# FCF_v2.net
KiCad netlist of a schematic drawn in EAGLE
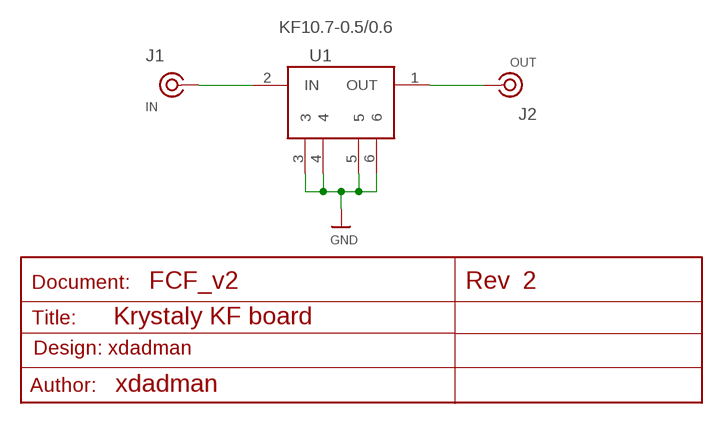
[diagram p0: schematic, sheet 1]

(export (version "E")
  (design (tool "Eeschema 10.0.6"))
  (components
    (comp (ref "J1")
      (value "IN")
      (footprint "eagle-import:SLIM_COAX_PAD")
      (libsource (lib "eagle-import") (part "COAX"))
    )
    (comp (ref "J2")
      (value "OUT")
      (footprint "eagle-import:SLIM_COAX_PAD")
      (libsource (lib "eagle-import") (part "COAX"))
    )
    (comp (ref "U1")
      (value "KF10.7-0.5/0.6")
      (footprint "eagle-import:KF-17")
      (libsource (lib "eagle-import") (part "KF10.7-0.5/0.6"))
    )
  )
  (nets
    (net (code "1") (name "GND") (class "Default")
      (node (ref "U1") (pin "3") (pinfunction "3_3") (pintype "bidirectional"))
      (node (ref "U1") (pin "4") (pinfunction "4_4") (pintype "bidirectional"))
      (node (ref "U1") (pin "5") (pinfunction "5_5") (pintype "bidirectional"))
      (node (ref "U1") (pin "6") (pinfunction "6_6") (pintype "bidirectional"))
    )
    (net (code "2") (name "Net-(J1A-1)") (class "Default")
      (node (ref "J1") (pin "SIG") (pinfunction "1_SIG") (pintype "passive"))
      (node (ref "U1") (pin "2") (pinfunction "IN_2") (pintype "bidirectional"))
    )
    (net (code "3") (name "Net-(J2A-1)") (class "Default")
      (node (ref "J2") (pin "SIG") (pinfunction "1_SIG") (pintype "passive"))
      (node (ref "U1") (pin "1") (pinfunction "OUT_1") (pintype "bidirectional"))
    )
  )
)
